# 2_3.net
KiCad netlist of a schematic drawn in EAGLE
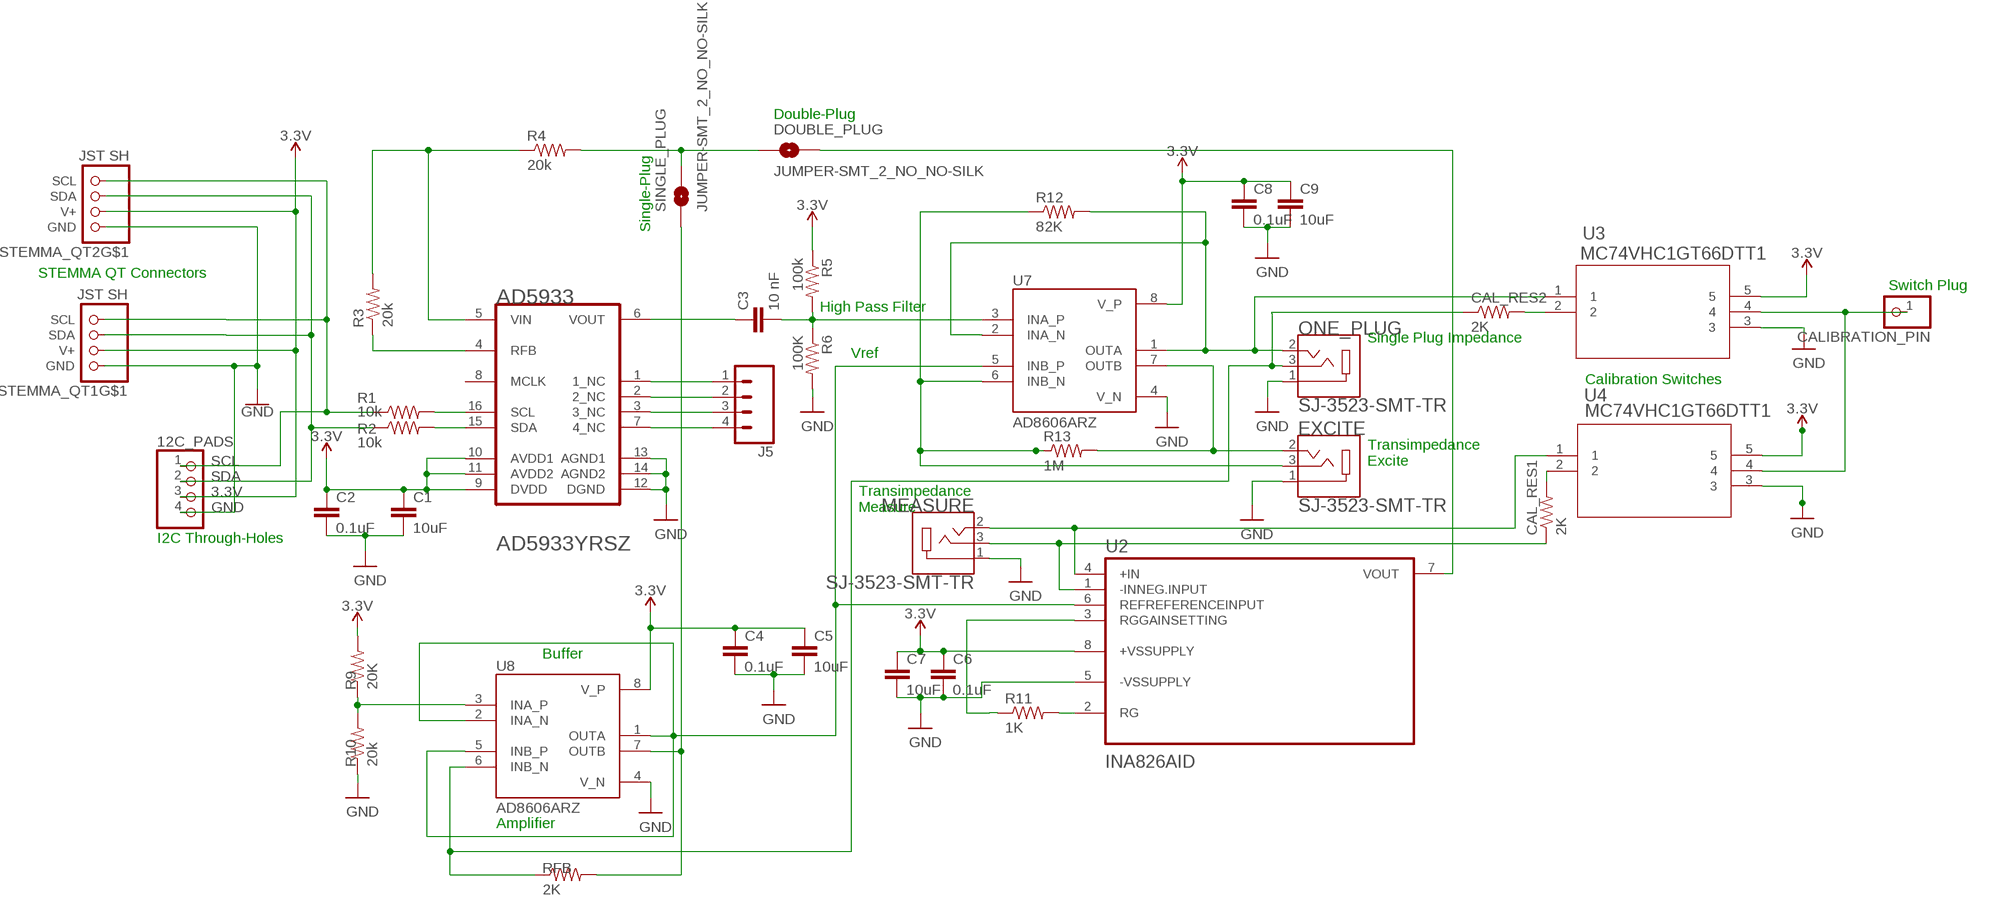
[diagram p0: schematic, sheet 1]

(export (version "E")
  (design (tool "Eeschema 10.0.6"))
  (components
    (comp (ref "12C_PADS")
      (value "PINHD-1X4")
      (footprint "eagle-import:1X04")
      (libsource (lib "eagle-import") (part "PINHD-1X4"))
    )
    (comp (ref "AD5933")
      (value "ANALOG_DEVICES_AD5933YRSZANALOG_DEVICES_AD5933YRSZ_0_0")
      (footprint "eagle-import:ANALOG_DEVICES_AD5933YRSZ_0")
      (fields (field (name "MF") "Analog Devices") (field (name "MPN") "AD5933YRSZ"))
      (libsource (lib "eagle-import") (part "ANALOG_DEVICES_AD5933YRSZANALOG_DEVICES_AD5933YRSZ_0_0"))
    )
    (comp (ref "C1")
      (value "10uF")
      (footprint "eagle-import:C0603")
      (libsource (lib "eagle-import") (part "C-EUC0603"))
    )
    (comp (ref "C2")
      (value "0.1uF")
      (footprint "eagle-import:C0603")
      (libsource (lib "eagle-import") (part "C-EUC0603"))
    )
    (comp (ref "C3")
      (value "10 nF")
      (footprint "eagle-import:C0603")
      (libsource (lib "eagle-import") (part "C-EUC0603"))
    )
    (comp (ref "C4")
      (value "0.1uF")
      (footprint "eagle-import:C0603")
      (libsource (lib "eagle-import") (part "C-EUC0603"))
    )
    (comp (ref "C5")
      (value "10uF")
      (footprint "eagle-import:C0603")
      (libsource (lib "eagle-import") (part "C-EUC0603"))
    )
    (comp (ref "C6")
      (value "0.1uF")
      (footprint "eagle-import:C0603")
      (libsource (lib "eagle-import") (part "C-EUC0603"))
    )
    (comp (ref "C7")
      (value "10uF")
      (footprint "eagle-import:C0603")
      (libsource (lib "eagle-import") (part "C-EUC0603"))
    )
    (comp (ref "C8")
      (value "0.1uF")
      (footprint "eagle-import:C0603")
      (libsource (lib "eagle-import") (part "C-EUC0603"))
    )
    (comp (ref "C9")
      (value "10uF")
      (footprint "eagle-import:C0603")
      (libsource (lib "eagle-import") (part "C-EUC0603"))
    )
    (comp (ref "CALIBRATION_PIN")
      (value "PINHD-1X1")
      (footprint "eagle-import:1X01")
      (libsource (lib "eagle-import") (part "PINHD-1X1"))
    )
    (comp (ref "CAL_RES1")
      (value "2K")
      (footprint "eagle-import:R0603")
      (libsource (lib "eagle-import") (part "R-US_R0603"))
    )
    (comp (ref "CAL_RES2")
      (value "2K")
      (footprint "eagle-import:R0603")
      (libsource (lib "eagle-import") (part "R-US_R0603"))
    )
    (comp (ref "DOUBLE_PLUG")
      (value "JUMPER-SMT_2_NO_NO-SILK")
      (footprint "eagle-import:SMT-JUMPER_2_NO_NO-SILK")
      (libsource (lib "eagle-import") (part "JUMPER-SMT_2_NO_NO-SILK"))
    )
    (comp (ref "EXCITE")
      (value "SJ-3523-SMT-TR")
      (footprint "eagle-import:CUI_SJ-3523-SMT-TR")
      (fields (field (name "MF") "CUI Devices"))
      (libsource (lib "eagle-import") (part "SJ-3523-SMT-TR"))
    )
    (comp (ref "J5")
      (value "CONN_04")
      (footprint "eagle-import:1X04")
      (libsource (lib "eagle-import") (part "CONN_04"))
    )
    (comp (ref "MEASURE")
      (value "SJ-3523-SMT-TR")
      (footprint "eagle-import:CUI_SJ-3523-SMT-TR")
      (fields (field (name "MF") "CUI Devices"))
      (libsource (lib "eagle-import") (part "SJ-3523-SMT-TR"))
    )
    (comp (ref "ONE_PLUG")
      (value "SJ-3523-SMT-TR")
      (footprint "eagle-import:CUI_SJ-3523-SMT-TR")
      (fields (field (name "MF") "CUI Devices"))
      (libsource (lib "eagle-import") (part "SJ-3523-SMT-TR"))
    )
    (comp (ref "R1")
      (value "10k")
      (footprint "eagle-import:R0603")
      (libsource (lib "eagle-import") (part "R-US_R0603"))
    )
    (comp (ref "R2")
      (value "10k")
      (footprint "eagle-import:R0603")
      (libsource (lib "eagle-import") (part "R-US_R0603"))
    )
    (comp (ref "R3")
      (value "20k")
      (footprint "eagle-import:R0603")
      (libsource (lib "eagle-import") (part "R-US_R0603"))
    )
    (comp (ref "R4")
      (value "20k")
      (footprint "eagle-import:R0603")
      (libsource (lib "eagle-import") (part "R-US_R0603"))
    )
    (comp (ref "R5")
      (value "100k")
      (footprint "eagle-import:R0603")
      (libsource (lib "eagle-import") (part "R-US_R0603"))
    )
    (comp (ref "R6")
      (value "100K")
      (footprint "eagle-import:R0603")
      (libsource (lib "eagle-import") (part "R-US_R0603"))
    )
    (comp (ref "R9")
      (value "20K")
      (footprint "eagle-import:R0603")
      (libsource (lib "eagle-import") (part "R-US_R0603"))
    )
    (comp (ref "R10")
      (value "20k")
      (footprint "eagle-import:R0603")
      (libsource (lib "eagle-import") (part "R-US_R0603"))
    )
    (comp (ref "R11")
      (value "1K")
      (footprint "eagle-import:R0603")
      (libsource (lib "eagle-import") (part "R-US_R0603"))
    )
    (comp (ref "R12")
      (value "82K")
      (footprint "eagle-import:R0603")
      (libsource (lib "eagle-import") (part "R-US_R0603"))
    )
    (comp (ref "R13")
      (value "1M")
      (footprint "eagle-import:R0603")
      (libsource (lib "eagle-import") (part "R-US_R0603"))
    )
    (comp (ref "RFB")
      (value "2K")
      (footprint "eagle-import:R0603")
      (libsource (lib "eagle-import") (part "R-US_R0603"))
    )
    (comp (ref "SINGLE_PLUG")
      (value "JUMPER-SMT_2_NO_NO-SILK")
      (footprint "eagle-import:SMT-JUMPER_2_NO_NO-SILK")
      (libsource (lib "eagle-import") (part "JUMPER-SMT_2_NO_NO-SILK"))
    )
    (comp (ref "STEMMA_QT1")
      (value "JST SH")
      (footprint "eagle-import:JST_SH4_RA")
      (libsource (lib "eagle-import") (part "STEMMA_I2C_QTRA"))
    )
    (comp (ref "STEMMA_QT2")
      (value "JST SH")
      (footprint "eagle-import:JST_SH4_RA")
      (libsource (lib "eagle-import") (part "STEMMA_I2C_QTRA"))
    )
    (comp (ref "U2")
      (value "INA826AID")
      (footprint "eagle-import:SOIC127P599X175-8N")
      (fields (field (name "MF") "Texas Instruments"))
      (libsource (lib "eagle-import") (part "INA826AID"))
    )
    (comp (ref "U3")
      (value "MC74VHC1GT66DTT1")
      (footprint "eagle-import:TSOP5_1P65X3P15_ONS")
      (fields (field (name "COPYRIGHT") "Copyright (C) 2024 Ultra Librarian. All rights reserved."))
      (libsource (lib "eagle-import") (part "MC74VHC1GT66DTT1"))
    )
    (comp (ref "U4")
      (value "MC74VHC1GT66DTT1")
      (footprint "eagle-import:TSOP5_1P65X3P15_ONS")
      (fields (field (name "COPYRIGHT") "Copyright (C) 2024 Ultra Librarian. All rights reserved."))
      (libsource (lib "eagle-import") (part "MC74VHC1GT66DTT1"))
    )
    (comp (ref "U7")
      (value "AD8606ARZ")
      (footprint "eagle-import:SOIC127P600X175-8N")
      (fields (field (name "MF") "Analog Devices"))
      (libsource (lib "eagle-import") (part "AD8606ARZ"))
    )
    (comp (ref "U8")
      (value "AD8606ARZ")
      (footprint "eagle-import:SOIC127P600X175-8N")
      (fields (field (name "MF") "Analog Devices"))
      (libsource (lib "eagle-import") (part "AD8606ARZ"))
    )
  )
  (nets
    (net (code "1") (name "/SCL") (class "Default")
      (node (ref "12C_PADS") (pin "1") (pinfunction "1_1") (pintype "passive"))
      (node (ref "R1") (pin "1") (pinfunction "1_1") (pintype "passive"))
      (node (ref "STEMMA_QT1") (pin "4") (pinfunction "SCL_4") (pintype "passive"))
      (node (ref "STEMMA_QT2") (pin "4") (pinfunction "SCL_4") (pintype "passive"))
    )
    (net (code "2") (name "/SDA") (class "Default")
      (node (ref "12C_PADS") (pin "2") (pinfunction "2_2") (pintype "passive"))
      (node (ref "R2") (pin "1") (pinfunction "1_1") (pintype "passive"))
      (node (ref "STEMMA_QT1") (pin "3") (pinfunction "SDA_3") (pintype "passive"))
      (node (ref "STEMMA_QT2") (pin "3") (pinfunction "SDA_3") (pintype "passive"))
    )
    (net (code "3") (name "3.3V") (class "Default")
      (node (ref "12C_PADS") (pin "3") (pinfunction "3_3") (pintype "passive"))
      (node (ref "AD5933") (pin "10") (pinfunction "AVDD1_10") (pintype "power_in"))
      (node (ref "AD5933") (pin "11") (pinfunction "AVDD2_11") (pintype "power_in"))
      (node (ref "AD5933") (pin "9") (pinfunction "DVDD_9") (pintype "power_in"))
      (node (ref "C1") (pin "1") (pinfunction "1_1") (pintype "passive"))
      (node (ref "C2") (pin "1") (pinfunction "1_1") (pintype "passive"))
      (node (ref "C4") (pin "1") (pinfunction "1_1") (pintype "passive"))
      (node (ref "C5") (pin "1") (pinfunction "1_1") (pintype "passive"))
      (node (ref "C6") (pin "1") (pinfunction "1_1") (pintype "passive"))
      (node (ref "C7") (pin "1") (pinfunction "1_1") (pintype "passive"))
      (node (ref "C8") (pin "1") (pinfunction "1_1") (pintype "passive"))
      (node (ref "C9") (pin "1") (pinfunction "1_1") (pintype "passive"))
      (node (ref "R5") (pin "1") (pinfunction "1_1") (pintype "passive"))
      (node (ref "R9") (pin "2") (pinfunction "2_2") (pintype "passive"))
      (node (ref "STEMMA_QT1") (pin "2") (pinfunction "V+_2") (pintype "passive"))
      (node (ref "STEMMA_QT2") (pin "2") (pinfunction "V+_2") (pintype "passive"))
      (node (ref "U2") (pin "8") (pinfunction "+VSSUPPLY_8") (pintype "bidirectional"))
      (node (ref "U3") (pin "5") (pinfunction "5_5") (pintype "passive"))
      (node (ref "U4") (pin "5") (pinfunction "5_5") (pintype "passive"))
      (node (ref "U7") (pin "8") (pinfunction "V_P_8") (pintype "power_in"))
      (node (ref "U8") (pin "8") (pinfunction "V_P_8") (pintype "power_in"))
    )
    (net (code "4") (name "GND") (class "Default")
      (node (ref "12C_PADS") (pin "4") (pinfunction "4_4") (pintype "passive"))
      (node (ref "AD5933") (pin "12") (pinfunction "DGND_12") (pintype "power_in"))
      (node (ref "AD5933") (pin "13") (pinfunction "AGND1_13") (pintype "power_in"))
      (node (ref "AD5933") (pin "14") (pinfunction "AGND2_14") (pintype "power_in"))
      (node (ref "C1") (pin "2") (pinfunction "2_2") (pintype "passive"))
      (node (ref "C2") (pin "2") (pinfunction "2_2") (pintype "passive"))
      (node (ref "C4") (pin "2") (pinfunction "2_2") (pintype "passive"))
      (node (ref "C5") (pin "2") (pinfunction "2_2") (pintype "passive"))
      (node (ref "C6") (pin "2") (pinfunction "2_2") (pintype "passive"))
      (node (ref "C7") (pin "2") (pinfunction "2_2") (pintype "passive"))
      (node (ref "C8") (pin "2") (pinfunction "2_2") (pintype "passive"))
      (node (ref "C9") (pin "2") (pinfunction "2_2") (pintype "passive"))
      (node (ref "EXCITE") (pin "1") (pinfunction "1_1") (pintype "passive"))
      (node (ref "MEASURE") (pin "1") (pinfunction "1_1") (pintype "passive"))
      (node (ref "ONE_PLUG") (pin "1") (pinfunction "1_1") (pintype "passive"))
      (node (ref "R10") (pin "1") (pinfunction "1_1") (pintype "passive"))
      (node (ref "R6") (pin "2") (pinfunction "2_2") (pintype "passive"))
      (node (ref "STEMMA_QT1") (pin "1") (pinfunction "GND_1") (pintype "passive"))
      (node (ref "STEMMA_QT2") (pin "1") (pinfunction "GND_1") (pintype "passive"))
      (node (ref "U2") (pin "5") (pinfunction "-VSSUPPLY_5") (pintype "bidirectional"))
      (node (ref "U3") (pin "3") (pinfunction "3_3") (pintype "passive"))
      (node (ref "U4") (pin "3") (pinfunction "3_3") (pintype "passive"))
      (node (ref "U7") (pin "4") (pinfunction "V_N_4") (pintype "power_in"))
      (node (ref "U8") (pin "4") (pinfunction "V_N_4") (pintype "power_in"))
    )
    (net (code "5") (name "Net-(AD5933-1_NC)") (class "Default")
      (node (ref "AD5933") (pin "1") (pinfunction "1_NC_1") (pintype "passive"))
      (node (ref "J5") (pin "1") (pinfunction "1_1") (pintype "passive"))
    )
    (net (code "6") (name "Net-(AD5933-2_NC)") (class "Default")
      (node (ref "AD5933") (pin "2") (pinfunction "2_NC_2") (pintype "passive"))
      (node (ref "J5") (pin "2") (pinfunction "2_2") (pintype "passive"))
    )
    (net (code "7") (name "Net-(AD5933-3_NC)") (class "Default")
      (node (ref "AD5933") (pin "3") (pinfunction "3_NC_3") (pintype "passive"))
      (node (ref "J5") (pin "3") (pinfunction "3_3") (pintype "passive"))
    )
    (net (code "8") (name "Net-(AD5933-4_NC)") (class "Default")
      (node (ref "AD5933") (pin "7") (pinfunction "4_NC_7") (pintype "passive"))
      (node (ref "J5") (pin "4") (pinfunction "4_4") (pintype "passive"))
    )
    (net (code "9") (name "Net-(AD5933-RFB)") (class "Default")
      (node (ref "AD5933") (pin "4") (pinfunction "RFB_4") (pintype "input"))
      (node (ref "R3") (pin "1") (pinfunction "1_1") (pintype "passive"))
    )
    (net (code "10") (name "Net-(AD5933-SCL)") (class "Default")
      (node (ref "AD5933") (pin "16") (pinfunction "SCL_16") (pintype "input"))
      (node (ref "R1") (pin "2") (pinfunction "2_2") (pintype "passive"))
    )
    (net (code "11") (name "Net-(AD5933-SDA)") (class "Default")
      (node (ref "AD5933") (pin "15") (pinfunction "SDA_15") (pintype "bidirectional"))
      (node (ref "R2") (pin "2") (pinfunction "2_2") (pintype "passive"))
    )
    (net (code "12") (name "Net-(AD5933-VIN)") (class "Default")
      (node (ref "AD5933") (pin "5") (pinfunction "VIN_5") (pintype "input"))
      (node (ref "R3") (pin "2") (pinfunction "2_2") (pintype "passive"))
      (node (ref "R4") (pin "1") (pinfunction "1_1") (pintype "passive"))
    )
    (net (code "13") (name "Net-(AD5933-VOUT)") (class "Default")
      (node (ref "AD5933") (pin "6") (pinfunction "VOUT_6") (pintype "output"))
      (node (ref "C3") (pin "1") (pinfunction "1_1") (pintype "passive"))
    )
    (net (code "14") (name "Net-(CALIBRATION_PIN-Pad1)") (class "Default")
      (node (ref "CALIBRATION_PIN") (pin "1") (pinfunction "1_1") (pintype "passive"))
      (node (ref "U3") (pin "4") (pinfunction "4_4") (pintype "passive"))
      (node (ref "U4") (pin "4") (pinfunction "4_4") (pintype "passive"))
    )
    (net (code "15") (name "Net-(CAL_RES1-Pad2)") (class "Default")
      (node (ref "CAL_RES1") (pin "2") (pinfunction "2_2") (pintype "passive"))
      (node (ref "U4") (pin "2") (pinfunction "2_2") (pintype "passive"))
    )
    (net (code "16") (name "Net-(CAL_RES2-Pad2)") (class "Default")
      (node (ref "CAL_RES2") (pin "2") (pinfunction "2_2") (pintype "passive"))
      (node (ref "U3") (pin "2") (pinfunction "2_2") (pintype "passive"))
    )
    (net (code "17") (name "Net-(DOUBLE_PLUG-Pad1)") (class "Default")
      (node (ref "DOUBLE_PLUG") (pin "1") (pinfunction "1_1") (pintype "passive"))
      (node (ref "R4") (pin "2") (pinfunction "2_2") (pintype "passive"))
      (node (ref "SINGLE_PLUG") (pin "2") (pinfunction "2_2") (pintype "passive"))
    )
    (net (code "18") (name "Net-(U2-+IN)") (class "Default")
      (node (ref "MEASURE") (pin "2") (pinfunction "2_2") (pintype "passive"))
      (node (ref "U2") (pin "4") (pinfunction "+IN_4") (pintype "input"))
      (node (ref "U4") (pin "1") (pinfunction "1_1") (pintype "passive"))
    )
    (net (code "19") (name "Net-(U2--INNEG.INPUT)") (class "Default")
      (node (ref "CAL_RES1") (pin "1") (pinfunction "1_1") (pintype "passive"))
      (node (ref "MEASURE") (pin "3") (pinfunction "3_3") (pintype "passive"))
      (node (ref "U2") (pin "1") (pinfunction "-INNEG.INPUT_1") (pintype "input"))
    )
    (net (code "20") (name "Net-(U2-REFREFERENCEINPUT)") (class "Default")
      (node (ref "U2") (pin "6") (pinfunction "REFREFERENCEINPUT_6") (pintype "input"))
      (node (ref "U7") (pin "5") (pinfunction "INB_P_5") (pintype "input"))
      (node (ref "U8") (pin "1") (pinfunction "OUTA_1") (pintype "input"))
      (node (ref "U8") (pin "2") (pinfunction "INA_N_2") (pintype "input"))
      (node (ref "U8") (pin "5") (pinfunction "INB_P_5") (pintype "input"))
    )
    (net (code "21") (name "Net-(U2-RG)") (class "Default")
      (node (ref "R11") (pin "2") (pinfunction "2_2") (pintype "passive"))
      (node (ref "U2") (pin "2") (pinfunction "RG_2") (pintype "bidirectional"))
    )
    (net (code "22") (name "Net-(U2-RGGAINSETTING)") (class "Default")
      (node (ref "R11") (pin "1") (pinfunction "1_1") (pintype "passive"))
      (node (ref "U2") (pin "3") (pinfunction "RGGAINSETTING_3") (pintype "input"))
    )
    (net (code "23") (name "Net-(U2-VOUT)") (class "Default")
      (node (ref "DOUBLE_PLUG") (pin "2") (pinfunction "2_2") (pintype "passive"))
      (node (ref "U2") (pin "7") (pinfunction "VOUT_7") (pintype "output"))
    )
    (net (code "24") (name "Net-(U7-INA_N)") (class "Default")
      (node (ref "ONE_PLUG") (pin "2") (pinfunction "2_2") (pintype "passive"))
      (node (ref "R12") (pin "2") (pinfunction "2_2") (pintype "passive"))
      (node (ref "U3") (pin "1") (pinfunction "1_1") (pintype "passive"))
      (node (ref "U7") (pin "1") (pinfunction "OUTA_1") (pintype "input"))
      (node (ref "U7") (pin "2") (pinfunction "INA_N_2") (pintype "input"))
    )
    (net (code "25") (name "Net-(U7-INA_P)") (class "Default")
      (node (ref "C3") (pin "2") (pinfunction "2_2") (pintype "passive"))
      (node (ref "R5") (pin "2") (pinfunction "2_2") (pintype "passive"))
      (node (ref "R6") (pin "1") (pinfunction "1_1") (pintype "passive"))
      (node (ref "U7") (pin "3") (pinfunction "INA_P_3") (pintype "input"))
    )
    (net (code "26") (name "Net-(U7-INB_N)") (class "Default")
      (node (ref "EXCITE") (pin "3") (pinfunction "3_3") (pintype "passive"))
      (node (ref "R12") (pin "1") (pinfunction "1_1") (pintype "passive"))
      (node (ref "R13") (pin "1") (pinfunction "1_1") (pintype "passive"))
      (node (ref "U7") (pin "6") (pinfunction "INB_N_6") (pintype "input"))
    )
    (net (code "27") (name "Net-(U7-OUTB)") (class "Default")
      (node (ref "EXCITE") (pin "2") (pinfunction "2_2") (pintype "passive"))
      (node (ref "R13") (pin "2") (pinfunction "2_2") (pintype "passive"))
      (node (ref "U7") (pin "7") (pinfunction "OUTB_7") (pintype "input"))
    )
    (net (code "28") (name "Net-(U8-INA_P)") (class "Default")
      (node (ref "R10") (pin "2") (pinfunction "2_2") (pintype "passive"))
      (node (ref "R9") (pin "1") (pinfunction "1_1") (pintype "passive"))
      (node (ref "U8") (pin "3") (pinfunction "INA_P_3") (pintype "input"))
    )
    (net (code "29") (name "Net-(U8-INB_N)") (class "Default")
      (node (ref "CAL_RES2") (pin "1") (pinfunction "1_1") (pintype "passive"))
      (node (ref "ONE_PLUG") (pin "3") (pinfunction "3_3") (pintype "passive"))
      (node (ref "RFB") (pin "1") (pinfunction "1_1") (pintype "passive"))
      (node (ref "U8") (pin "6") (pinfunction "INB_N_6") (pintype "input"))
    )
    (net (code "30") (name "Net-(U8-OUTB)") (class "Default")
      (node (ref "RFB") (pin "2") (pinfunction "2_2") (pintype "passive"))
      (node (ref "SINGLE_PLUG") (pin "1") (pinfunction "1_1") (pintype "passive"))
      (node (ref "U8") (pin "7") (pinfunction "OUTB_7") (pintype "input"))
    )
    (net (code "31") (name "unconnected-(AD5933-MCLK-Pad8)") (class "Default")
      (node (ref "AD5933") (pin "8") (pinfunction "MCLK_8") (pintype "input"))
    )
  )
)
